# Sch2.net
KiCad netlist of a schematic drawn in Altium Designer
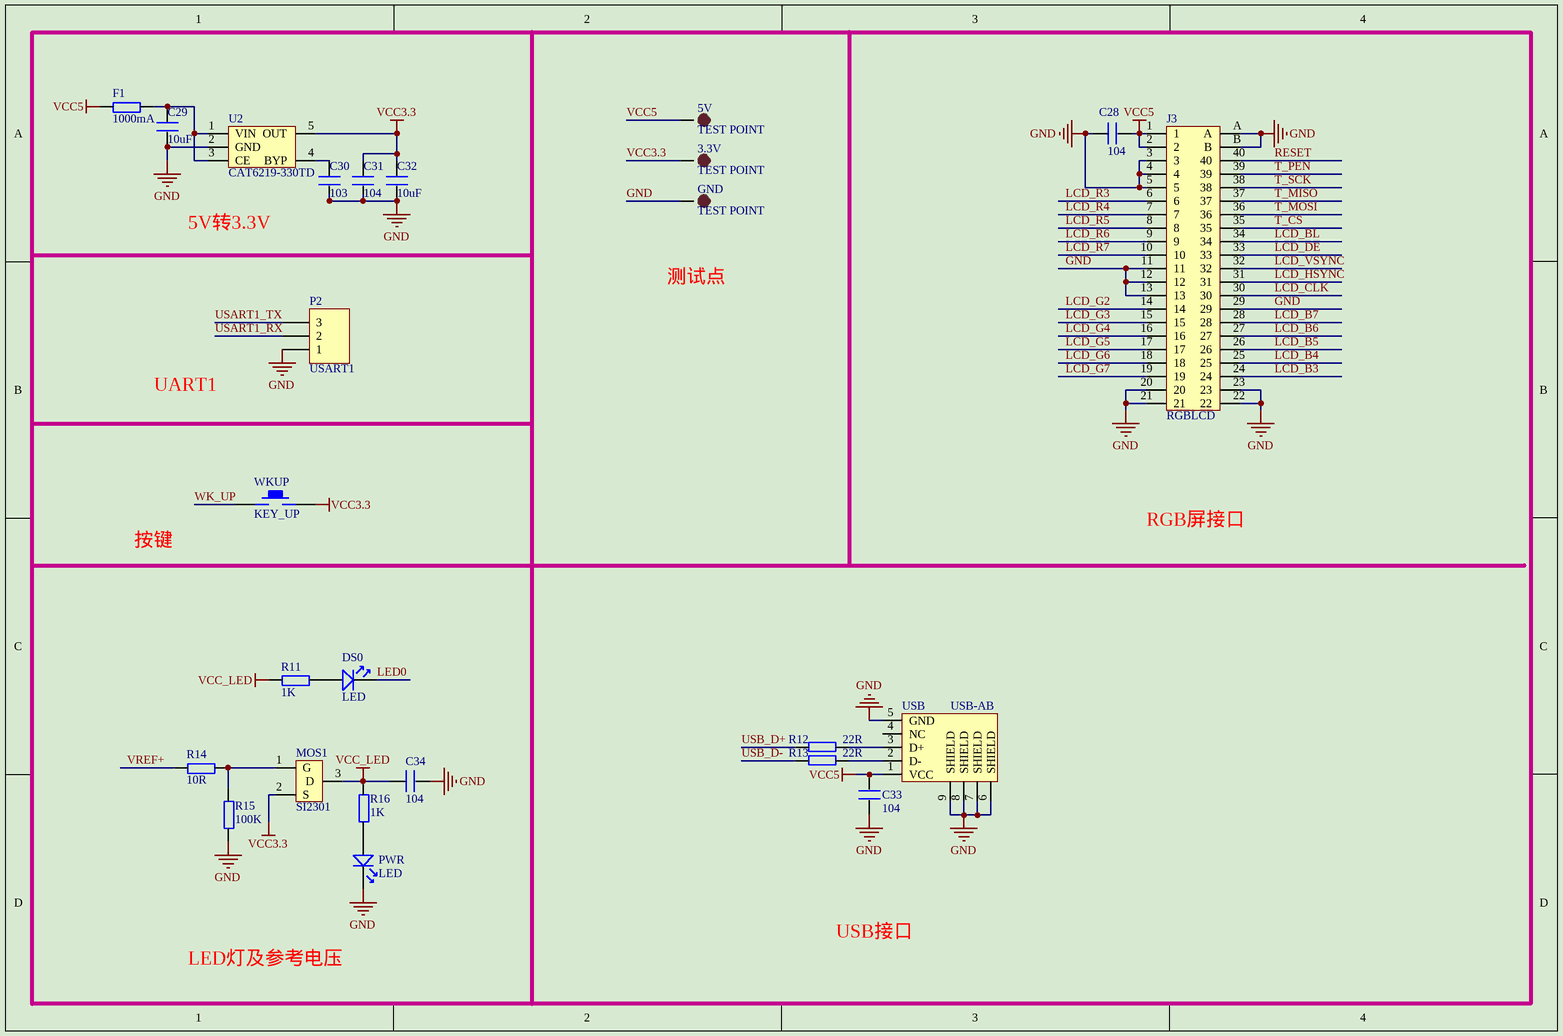
[diagram p0: Sch2.SchDoc]

(export (version "E")
  (design (tool "Eeschema 10.0.6"))
  (components
    (comp (ref "3.3V")
      (value "TEST POINT")
      (footprint "TP-1.5")
      (description "测试点")
      (libsource (lib "STM32F429_CORE") (part "TEST-POINT"))
    )
    (comp (ref "5V")
      (value "TEST POINT")
      (footprint "TP-1.5")
      (description "测试点")
      (libsource (lib "STM32F429_CORE") (part "TEST-POINT"))
    )
    (comp (ref "C28") (value "104") (footprint "0402") (libsource (lib "STM32F429_CORE") (part "C")))
    (comp (ref "C29") (value "10uF") (footprint "0603P") (libsource (lib "STM32F429_CORE") (part "C")))
    (comp (ref "C30") (value "103") (footprint "0402") (libsource (lib "STM32F429_CORE") (part "C")))
    (comp (ref "C31") (value "104") (footprint "0402") (libsource (lib "STM32F429_CORE") (part "C")))
    (comp (ref "C32") (value "10uF") (footprint "0603P") (libsource (lib "STM32F429_CORE") (part "C")))
    (comp (ref "C33") (value "104") (footprint "0402") (libsource (lib "STM32F429_CORE") (part "C")))
    (comp (ref "C34") (value "104") (footprint "0402") (libsource (lib "STM32F429_CORE") (part "C")))
    (comp (ref "DS0") (value "LED") (footprint "SMDLED-0603") (libsource (lib "STM32F429_CORE") (part "LED")))
    (comp (ref "F1") (value "1000mA") (footprint "0805") (libsource (lib "STM32F429_CORE") (part "R")))
    (comp (ref "GND")
      (value "TEST POINT")
      (footprint "TP-1.5")
      (description "测试点")
      (libsource (lib "STM32F429_CORE") (part "TEST-POINT"))
    )
    (comp (ref "J3")
      (value "RGBLCD")
      (footprint "FPC-TOP40")
      (description "FPC-40P-0.5mm")
      (libsource (lib "STM32F429_CORE") (part "FPC-40"))
    )
    (comp (ref "MOS1")
      (value "SI2301")
      (footprint "SO-G3/C2.5")
      (description "IRLML6401/SI2301")
      (libsource (lib "STM32F429_CORE") (part "MOS-P"))
    )
    (comp (ref "P2")
      (value "USART1")
      (footprint "HDR1X3")
      (description "Header, 3-Pin")
      (fields (field (name "PUBLISHER") "Altium Limited"))
      (libsource (lib "STM32F429_CORE") (part "Header 3"))
    )
    (comp (ref "PWR") (value "LED") (footprint "SMDLED-0603") (libsource (lib "STM32F429_CORE") (part "LED")))
    (comp (ref "R11") (value "1K") (footprint "0402") (libsource (lib "STM32F429_CORE") (part "R")))
    (comp (ref "R12") (value "22R") (footprint "0402") (libsource (lib "STM32F429_CORE") (part "R")))
    (comp (ref "R13") (value "22R") (footprint "0402") (libsource (lib "STM32F429_CORE") (part "R")))
    (comp (ref "R14") (value "10R") (footprint "0402") (libsource (lib "STM32F429_CORE") (part "R")))
    (comp (ref "R15") (value "100K") (footprint "0402") (libsource (lib "STM32F429_CORE") (part "R")))
    (comp (ref "R16") (value "1K") (footprint "0402") (libsource (lib "STM32F429_CORE") (part "R")))
    (comp (ref "U2")
      (value "CAT6219-330TD")
      (footprint "SOT-23-5")
      (description "3.3V 500mA LDO")
      (libsource (lib "STM32F429_CORE") (part "CAT6219-330TD"))
    )
    (comp (ref "USB")
      (value "USB-AB")
      (footprint "USB_AB")
      (description "MicroUSB")
      (libsource (lib "STM32F429_CORE") (part "USB-AB"))
    )
    (comp (ref "WKUP")
      (value "KEY_UP")
      (footprint "KEY_SOP3625")
      (libsource (lib "STM32F429_CORE") (part "KEY_M"))
    )
  )
  (nets
    (net (code "1") (name "/LCD_B3") (class "Default")
      (node (ref "J3") (pin "24") (pinfunction "24_24") (pintype "passive"))
    )
    (net (code "2") (name "/LCD_B4") (class "Default")
      (node (ref "J3") (pin "25") (pinfunction "25_25") (pintype "passive"))
    )
    (net (code "3") (name "/LCD_B5") (class "Default")
      (node (ref "J3") (pin "26") (pinfunction "26_26") (pintype "passive"))
    )
    (net (code "4") (name "/LCD_B6") (class "Default")
      (node (ref "J3") (pin "27") (pinfunction "27_27") (pintype "passive"))
    )
    (net (code "5") (name "/LCD_B7") (class "Default")
      (node (ref "J3") (pin "28") (pinfunction "28_28") (pintype "passive"))
    )
    (net (code "6") (name "/LCD_BL") (class "Default")
      (node (ref "J3") (pin "34") (pinfunction "34_34") (pintype "passive"))
    )
    (net (code "7") (name "/LCD_CLK") (class "Default")
      (node (ref "J3") (pin "30") (pinfunction "30_30") (pintype "passive"))
    )
    (net (code "8") (name "/LCD_DE") (class "Default")
      (node (ref "J3") (pin "33") (pinfunction "33_33") (pintype "passive"))
    )
    (net (code "9") (name "/LCD_G2") (class "Default")
      (node (ref "J3") (pin "14") (pinfunction "14_14") (pintype "passive"))
    )
    (net (code "10") (name "/LCD_G3") (class "Default")
      (node (ref "J3") (pin "15") (pinfunction "15_15") (pintype "passive"))
    )
    (net (code "11") (name "/LCD_G4") (class "Default")
      (node (ref "J3") (pin "16") (pinfunction "16_16") (pintype "passive"))
    )
    (net (code "12") (name "/LCD_G5") (class "Default")
      (node (ref "J3") (pin "17") (pinfunction "17_17") (pintype "passive"))
    )
    (net (code "13") (name "/LCD_G6") (class "Default")
      (node (ref "J3") (pin "18") (pinfunction "18_18") (pintype "passive"))
    )
    (net (code "14") (name "/LCD_G7") (class "Default")
      (node (ref "J3") (pin "19") (pinfunction "19_19") (pintype "passive"))
    )
    (net (code "15") (name "/LCD_HSYNC") (class "Default")
      (node (ref "J3") (pin "31") (pinfunction "31_31") (pintype "passive"))
    )
    (net (code "16") (name "/LCD_R3") (class "Default")
      (node (ref "J3") (pin "6") (pinfunction "6_6") (pintype "passive"))
    )
    (net (code "17") (name "/LCD_R4") (class "Default")
      (node (ref "J3") (pin "7") (pinfunction "7_7") (pintype "passive"))
    )
    (net (code "18") (name "/LCD_R5") (class "Default")
      (node (ref "J3") (pin "8") (pinfunction "8_8") (pintype "passive"))
    )
    (net (code "19") (name "/LCD_R6") (class "Default")
      (node (ref "J3") (pin "9") (pinfunction "9_9") (pintype "passive"))
    )
    (net (code "20") (name "/LCD_R7") (class "Default")
      (node (ref "J3") (pin "10") (pinfunction "10_10") (pintype "passive"))
    )
    (net (code "21") (name "/LCD_VSYNC") (class "Default")
      (node (ref "J3") (pin "32") (pinfunction "32_32") (pintype "passive"))
    )
    (net (code "22") (name "/LED0") (class "Default")
      (node (ref "DS0") (pin "2") (pinfunction "2_2") (pintype "passive"))
    )
    (net (code "23") (name "/RESET") (class "Default")
      (node (ref "J3") (pin "40") (pinfunction "40_40") (pintype "passive"))
    )
    (net (code "24") (name "/T_CS") (class "Default")
      (node (ref "J3") (pin "35") (pinfunction "35_35") (pintype "passive"))
    )
    (net (code "25") (name "/T_MISO") (class "Default")
      (node (ref "J3") (pin "37") (pinfunction "37_37") (pintype "passive"))
    )
    (net (code "26") (name "/T_MOSI") (class "Default")
      (node (ref "J3") (pin "36") (pinfunction "36_36") (pintype "passive"))
    )
    (net (code "27") (name "/T_PEN") (class "Default")
      (node (ref "J3") (pin "39") (pinfunction "39_39") (pintype "passive"))
    )
    (net (code "28") (name "/T_SCK") (class "Default")
      (node (ref "J3") (pin "38") (pinfunction "38_38") (pintype "passive"))
    )
    (net (code "29") (name "/USART1_RX") (class "Default")
      (node (ref "P2") (pin "2") (pinfunction "2_2") (pintype "passive"))
    )
    (net (code "30") (name "/USART1_TX") (class "Default")
      (node (ref "P2") (pin "3") (pinfunction "3_3") (pintype "passive"))
    )
    (net (code "31") (name "/USB_D+") (class "Default") (node (ref "R12") (pin "2") (pintype "passive")))
    (net (code "32") (name "/USB_D-") (class "Default") (node (ref "R13") (pin "2") (pintype "passive")))
    (net (code "33") (name "/VREF+") (class "Default") (node (ref "R14") (pin "1") (pintype "passive")))
    (net (code "34") (name "/WK_UP") (class "Default")
      (node (ref "WKUP") (pin "1") (pinfunction "1_1") (pintype "passive"))
    )
    (net (code "35") (name "GND") (class "Default")
      (node (ref "C28") (pin "2") (pintype "passive"))
      (node (ref "C29") (pin "1") (pintype "passive"))
      (node (ref "C30") (pin "1") (pintype "passive"))
      (node (ref "C31") (pin "1") (pintype "passive"))
      (node (ref "C32") (pin "1") (pintype "passive"))
      (node (ref "C33") (pin "2") (pintype "passive"))
      (node (ref "C34") (pin "1") (pintype "passive"))
      (node (ref "GND") (pin "1") (pinfunction "1_1") (pintype "passive"))
      (node (ref "J3") (pin "11") (pinfunction "11_11") (pintype "passive"))
      (node (ref "J3") (pin "12") (pinfunction "12_12") (pintype "passive"))
      (node (ref "J3") (pin "13") (pinfunction "13_13") (pintype "passive"))
      (node (ref "J3") (pin "20") (pinfunction "20_20") (pintype "passive"))
      (node (ref "J3") (pin "21") (pinfunction "21_21") (pintype "passive"))
      (node (ref "J3") (pin "22") (pinfunction "22_22") (pintype "passive"))
      (node (ref "J3") (pin "23") (pinfunction "23_23") (pintype "passive"))
      (node (ref "J3") (pin "29") (pinfunction "29_29") (pintype "passive"))
      (node (ref "J3") (pin "3") (pinfunction "3_3") (pintype "passive"))
      (node (ref "J3") (pin "4") (pinfunction "4_4") (pintype "passive"))
      (node (ref "J3") (pin "5") (pinfunction "5_5") (pintype "passive"))
      (node (ref "J3") (pin "A") (pinfunction "A_A") (pintype "passive"))
      (node (ref "J3") (pin "B") (pinfunction "B_B") (pintype "passive"))
      (node (ref "P2") (pin "1") (pinfunction "1_1") (pintype "passive"))
      (node (ref "PWR") (pin "2") (pinfunction "2_2") (pintype "passive"))
      (node (ref "R15") (pin "1") (pintype "passive"))
      (node (ref "U2") (pin "2") (pinfunction "GND_2") (pintype "passive"))
      (node (ref "USB") (pin "5") (pinfunction "GND_5") (pintype "passive"))
      (node (ref "USB") (pin "6") (pinfunction "SHIELD_6") (pintype "passive"))
      (node (ref "USB") (pin "7") (pinfunction "SHIELD_7") (pintype "passive"))
      (node (ref "USB") (pin "8") (pinfunction "SHIELD_8") (pintype "passive"))
      (node (ref "USB") (pin "9") (pinfunction "SHIELD_9") (pintype "passive"))
    )
    (net (code "36") (name "Net-(DS0-Pad1)") (class "Default")
      (node (ref "DS0") (pin "1") (pinfunction "1_1") (pintype "passive"))
      (node (ref "R11") (pin "2") (pintype "passive"))
    )
    (net (code "37") (name "Net-(MOS1-G)") (class "Default")
      (node (ref "MOS1") (pin "1") (pinfunction "G_1") (pintype "passive"))
      (node (ref "R14") (pin "2") (pintype "passive"))
      (node (ref "R15") (pin "2") (pintype "passive"))
    )
    (net (code "38") (name "Net-(PWR-Pad1)") (class "Default")
      (node (ref "PWR") (pin "1") (pinfunction "1_1") (pintype "passive"))
      (node (ref "R16") (pin "1") (pintype "passive"))
    )
    (net (code "39") (name "Net-(U2-BYP)") (class "Default")
      (node (ref "C30") (pin "2") (pintype "passive"))
      (node (ref "U2") (pin "4") (pinfunction "BYP_4") (pintype "passive"))
    )
    (net (code "40") (name "Net-(U2-CE)") (class "Default")
      (node (ref "C29") (pin "2") (pintype "passive"))
      (node (ref "F1") (pin "2") (pintype "passive"))
      (node (ref "U2") (pin "1") (pinfunction "VIN_1") (pintype "passive"))
      (node (ref "U2") (pin "3") (pinfunction "CE_3") (pintype "passive"))
    )
    (net (code "41") (name "Net-(USB-D+)") (class "Default")
      (node (ref "R12") (pin "1") (pintype "passive"))
      (node (ref "USB") (pin "3") (pinfunction "D+_3") (pintype "passive"))
    )
    (net (code "42") (name "Net-(USB-D-)") (class "Default")
      (node (ref "R13") (pin "1") (pintype "passive"))
      (node (ref "USB") (pin "2") (pinfunction "D-_2") (pintype "passive"))
    )
    (net (code "43") (name "VCC3.3") (class "Default")
      (node (ref "3.3V") (pin "1") (pinfunction "1_1") (pintype "passive"))
      (node (ref "C31") (pin "2") (pintype "passive"))
      (node (ref "C32") (pin "2") (pintype "passive"))
      (node (ref "MOS1") (pin "2") (pinfunction "S_2") (pintype "passive"))
      (node (ref "U2") (pin "5") (pinfunction "OUT_5") (pintype "passive"))
      (node (ref "WKUP") (pin "2") (pinfunction "2_2") (pintype "passive"))
    )
    (net (code "44") (name "VCC5") (class "Default")
      (node (ref "5V") (pin "1") (pinfunction "1_1") (pintype "passive"))
      (node (ref "C28") (pin "1") (pintype "passive"))
      (node (ref "C33") (pin "1") (pintype "passive"))
      (node (ref "F1") (pin "1") (pintype "passive"))
      (node (ref "J3") (pin "1") (pinfunction "1_1") (pintype "passive"))
      (node (ref "J3") (pin "2") (pinfunction "2_2") (pintype "passive"))
      (node (ref "USB") (pin "1") (pinfunction "VCC_1") (pintype "passive"))
    )
    (net (code "45") (name "VCC_LED") (class "Default")
      (node (ref "C34") (pin "2") (pintype "passive"))
      (node (ref "MOS1") (pin "3") (pinfunction "D_3") (pintype "passive"))
      (node (ref "R11") (pin "1") (pintype "passive"))
      (node (ref "R16") (pin "2") (pintype "passive"))
    )
    (net (code "46") (name "unconnected-(USB-NC-Pad4)") (class "Default")
      (node (ref "USB") (pin "4") (pinfunction "NC_4") (pintype "passive"))
    )
  )
)
